# V1.net
KiCad netlist of a schematic drawn in EAGLE
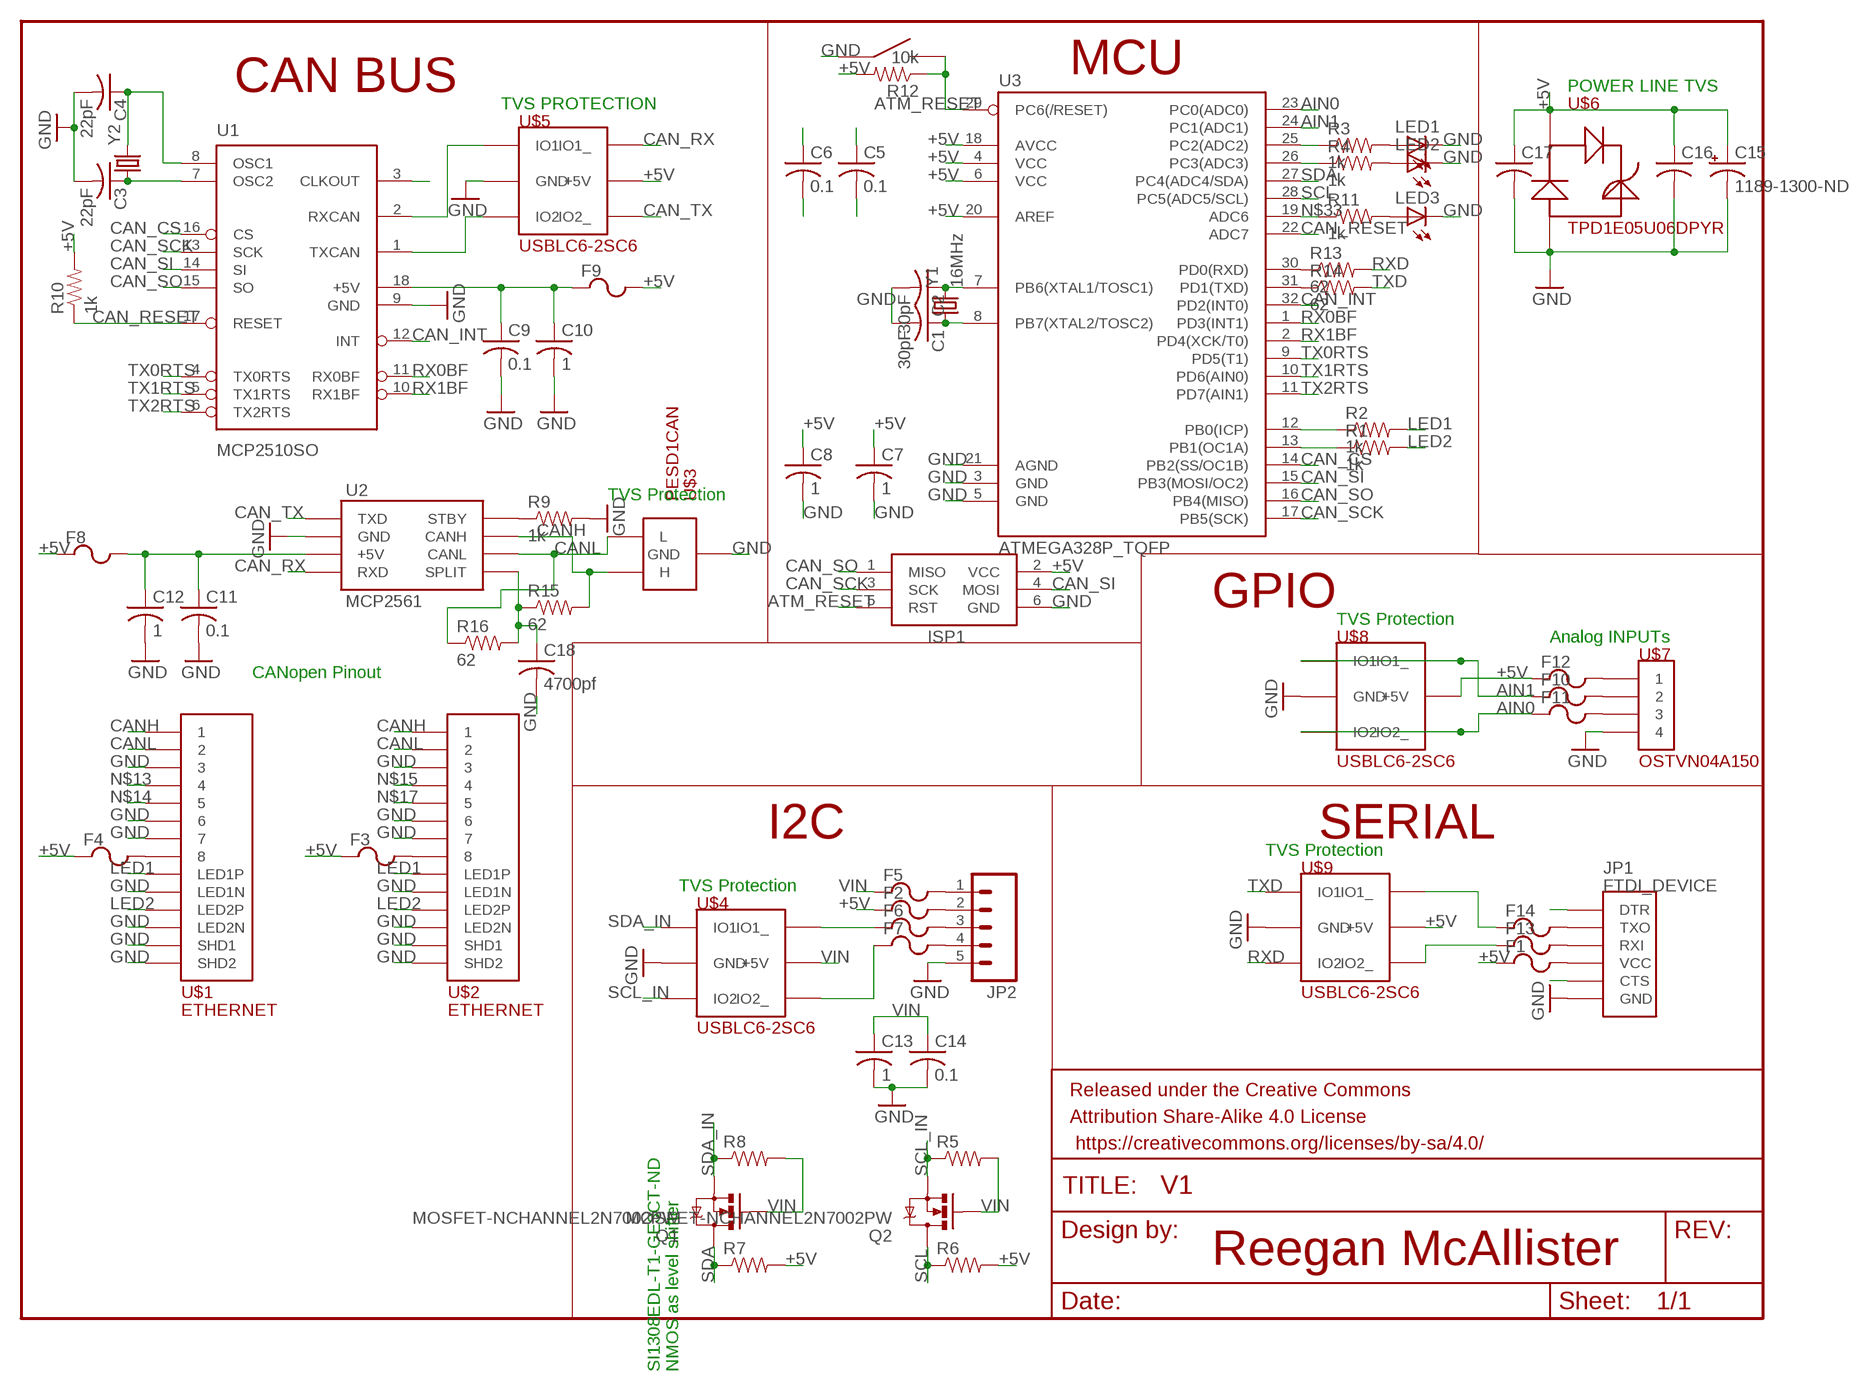
[diagram p0: schematic, sheet 1]

(export (version "E")
  (design (tool "Eeschema 10.0.6"))
  (components
    (comp (ref "C1")
      (value "30pF")
      (footprint "eagle-import:C0603K")
      (libsource (lib "eagle-import") (part "C-USC0603K"))
    )
    (comp (ref "C2")
      (value "30pF")
      (footprint "eagle-import:C0603K")
      (libsource (lib "eagle-import") (part "C-USC0603K"))
    )
    (comp (ref "C3")
      (value "22pF")
      (footprint "eagle-import:C0603K")
      (libsource (lib "eagle-import") (part "C-USC0603K"))
    )
    (comp (ref "C4")
      (value "22pF")
      (footprint "eagle-import:C0603K")
      (libsource (lib "eagle-import") (part "C-USC0603K"))
    )
    (comp (ref "C5")
      (value "0.1")
      (footprint "eagle-import:C0603K")
      (libsource (lib "eagle-import") (part "C-USC0603K"))
    )
    (comp (ref "C6")
      (value "0.1")
      (footprint "eagle-import:C0603K")
      (libsource (lib "eagle-import") (part "C-USC0603K"))
    )
    (comp (ref "C7")
      (value "1")
      (footprint "eagle-import:C0603K")
      (libsource (lib "eagle-import") (part "C-USC0603K"))
    )
    (comp (ref "C8")
      (value "1")
      (footprint "eagle-import:C0603K")
      (libsource (lib "eagle-import") (part "C-USC0603K"))
    )
    (comp (ref "C9")
      (value "0.1")
      (footprint "eagle-import:C0603K")
      (libsource (lib "eagle-import") (part "C-USC0603K"))
    )
    (comp (ref "C10")
      (value "1")
      (footprint "eagle-import:C0603K")
      (libsource (lib "eagle-import") (part "C-USC0603K"))
    )
    (comp (ref "C11")
      (value "0.1")
      (footprint "eagle-import:C0603K")
      (libsource (lib "eagle-import") (part "C-USC0603K"))
    )
    (comp (ref "C12")
      (value "1")
      (footprint "eagle-import:C0603K")
      (libsource (lib "eagle-import") (part "C-USC0603K"))
    )
    (comp (ref "C13")
      (value "1")
      (footprint "eagle-import:C0603K")
      (libsource (lib "eagle-import") (part "C-USC0603K"))
    )
    (comp (ref "C14")
      (value "0.1")
      (footprint "eagle-import:C0603K")
      (libsource (lib "eagle-import") (part "C-USC0603K"))
    )
    (comp (ref "C15")
      (value "1189-1300-ND")
      (footprint "eagle-import:1189-1300-ND")
      (libsource (lib "eagle-import") (part "1189-1300-ND"))
    )
    (comp (ref "C16")
      (value "C-USC0603K")
      (footprint "eagle-import:C0603K")
      (libsource (lib "eagle-import") (part "C-USC0603K"))
    )
    (comp (ref "C17")
      (value "C-USC0603K")
      (footprint "eagle-import:C0603K")
      (libsource (lib "eagle-import") (part "C-USC0603K"))
    )
    (comp (ref "C18")
      (value "4700pf")
      (footprint "eagle-import:C0603K")
      (libsource (lib "eagle-import") (part "C-USC0603K"))
    )
    (comp (ref "F1")
      (value "POLYFUSE")
      (footprint "eagle-import:1206")
      (libsource (lib "eagle-import") (part "POLYFUSE"))
    )
    (comp (ref "F2")
      (value "POLYFUSE")
      (footprint "eagle-import:1206")
      (libsource (lib "eagle-import") (part "POLYFUSE"))
    )
    (comp (ref "F3")
      (value "POLYFUSE")
      (footprint "eagle-import:1206")
      (libsource (lib "eagle-import") (part "POLYFUSE"))
    )
    (comp (ref "F4")
      (value "POLYFUSE")
      (footprint "eagle-import:1206")
      (libsource (lib "eagle-import") (part "POLYFUSE"))
    )
    (comp (ref "F5")
      (value "POLYFUSE")
      (footprint "eagle-import:1206")
      (libsource (lib "eagle-import") (part "POLYFUSE"))
    )
    (comp (ref "F6")
      (value "POLYFUSE")
      (footprint "eagle-import:1206")
      (libsource (lib "eagle-import") (part "POLYFUSE"))
    )
    (comp (ref "F7")
      (value "POLYFUSE")
      (footprint "eagle-import:1206")
      (libsource (lib "eagle-import") (part "POLYFUSE"))
    )
    (comp (ref "F8")
      (value "POLYFUSE")
      (footprint "eagle-import:1206")
      (libsource (lib "eagle-import") (part "POLYFUSE"))
    )
    (comp (ref "F9")
      (value "POLYFUSE")
      (footprint "eagle-import:1206")
      (libsource (lib "eagle-import") (part "POLYFUSE"))
    )
    (comp (ref "F10")
      (value "POLYFUSE")
      (footprint "eagle-import:1206")
      (libsource (lib "eagle-import") (part "POLYFUSE"))
    )
    (comp (ref "F11")
      (value "POLYFUSE")
      (footprint "eagle-import:1206")
      (libsource (lib "eagle-import") (part "POLYFUSE"))
    )
    (comp (ref "F12")
      (value "POLYFUSE")
      (footprint "eagle-import:1206")
      (libsource (lib "eagle-import") (part "POLYFUSE"))
    )
    (comp (ref "F13")
      (value "POLYFUSE")
      (footprint "eagle-import:1206")
      (libsource (lib "eagle-import") (part "POLYFUSE"))
    )
    (comp (ref "F14")
      (value "POLYFUSE")
      (footprint "eagle-import:1206")
      (libsource (lib "eagle-import") (part "POLYFUSE"))
    )
    (comp (ref "FRAME1")
      (value "FRAME-LETTERNO_PACKAGE")
      (footprint "eagle-import:DUMMY")
      (fields (field (name "DESIGNER") "Nobody"))
      (libsource (lib "eagle-import") (part "FRAME-LETTERNO_PACKAGE"))
    )
    (comp (ref "ISP1")
      (value "AVRISP-BOX")
      (footprint "eagle-import:AVRISP-BOX")
      (libsource (lib "eagle-import") (part "AVRISP-BOX"))
    )
    (comp (ref "JP1")
      (value "FTDI_DEVICE")
      (footprint "eagle-import:FTDI_DEVICE_SIDE")
      (libsource (lib "eagle-import") (part "FTDI_DEVICE"))
    )
    (comp (ref "JP2")
      (value "M05NO_SILK")
      (footprint "eagle-import:1X05_NO_SILK")
      (libsource (lib "eagle-import") (part "M05NO_SILK"))
    )
    (comp (ref "LED1")
      (value "LEDCHIPLED_0805")
      (footprint "eagle-import:CHIPLED_0805")
      (libsource (lib "eagle-import") (part "LEDCHIPLED_0805"))
    )
    (comp (ref "LED2")
      (value "LEDCHIPLED_0805")
      (footprint "eagle-import:CHIPLED_0805")
      (libsource (lib "eagle-import") (part "LEDCHIPLED_0805"))
    )
    (comp (ref "LED3")
      (value "LEDCHIPLED_0805")
      (footprint "eagle-import:CHIPLED_0805")
      (libsource (lib "eagle-import") (part "LEDCHIPLED_0805"))
    )
    (comp (ref "Q1")
      (value "MOSFET-NCHANNEL2N7002PW")
      (footprint "eagle-import:SOT323")
      (libsource (lib "eagle-import") (part "MOSFET-NCHANNEL2N7002PW"))
    )
    (comp (ref "Q2")
      (value "MOSFET-NCHANNEL2N7002PW")
      (footprint "eagle-import:SOT323")
      (libsource (lib "eagle-import") (part "MOSFET-NCHANNEL2N7002PW"))
    )
    (comp (ref "R1")
      (value "1k")
      (footprint "eagle-import:0603-RES")
      (libsource (lib "eagle-import") (part "RESISTOR0603-RES"))
    )
    (comp (ref "R2")
      (value "1k")
      (footprint "eagle-import:0603-RES")
      (libsource (lib "eagle-import") (part "RESISTOR0603-RES"))
    )
    (comp (ref "R3")
      (value "1k")
      (footprint "eagle-import:0603-RES")
      (libsource (lib "eagle-import") (part "RESISTOR0603-RES"))
    )
    (comp (ref "R4")
      (value "1k")
      (footprint "eagle-import:0603-RES")
      (libsource (lib "eagle-import") (part "RESISTOR0603-RES"))
    )
    (comp (ref "R5")
      (value "RESISTOR0603-RES")
      (footprint "eagle-import:0603-RES")
      (libsource (lib "eagle-import") (part "RESISTOR0603-RES"))
    )
    (comp (ref "R6")
      (value "RESISTOR0603-RES")
      (footprint "eagle-import:0603-RES")
      (libsource (lib "eagle-import") (part "RESISTOR0603-RES"))
    )
    (comp (ref "R7")
      (value "RESISTOR0603-RES")
      (footprint "eagle-import:0603-RES")
      (libsource (lib "eagle-import") (part "RESISTOR0603-RES"))
    )
    (comp (ref "R8")
      (value "RESISTOR0603-RES")
      (footprint "eagle-import:0603-RES")
      (libsource (lib "eagle-import") (part "RESISTOR0603-RES"))
    )
    (comp (ref "R9")
      (value "1k")
      (footprint "eagle-import:0603-RES")
      (libsource (lib "eagle-import") (part "RESISTOR0603-RES"))
    )
    (comp (ref "R10")
      (value "1k")
      (footprint "eagle-import:0603-RES")
      (libsource (lib "eagle-import") (part "RESISTOR0603-RES"))
    )
    (comp (ref "R11")
      (value "1k")
      (footprint "eagle-import:0603-RES")
      (libsource (lib "eagle-import") (part "RESISTOR0603-RES"))
    )
    (comp (ref "R12")
      (value "10k")
      (footprint "eagle-import:0603-RES")
      (libsource (lib "eagle-import") (part "RESISTOR0603-RES"))
    )
    (comp (ref "R13")
      (value "62")
      (footprint "eagle-import:0603-RES")
      (libsource (lib "eagle-import") (part "RESISTOR0603-RES"))
    )
    (comp (ref "R14")
      (value "62")
      (footprint "eagle-import:0603-RES")
      (libsource (lib "eagle-import") (part "RESISTOR0603-RES"))
    )
    (comp (ref "R15")
      (value "62")
      (footprint "eagle-import:0603-RES")
      (libsource (lib "eagle-import") (part "RESISTOR0603-RES"))
    )
    (comp (ref "R16")
      (value "62")
      (footprint "eagle-import:0603-RES")
      (libsource (lib "eagle-import") (part "RESISTOR0603-RES"))
    )
    (comp (ref "U$1")
      (value "ETHERNET")
      (footprint "eagle-import:A122645-ND")
      (libsource (lib "eagle-import") (part "ETHERNET"))
    )
    (comp (ref "U$2")
      (value "ETHERNET")
      (footprint "eagle-import:A122645-ND")
      (libsource (lib "eagle-import") (part "ETHERNET"))
    )
    (comp (ref "U$3")
      (value "PESD1CAN")
      (footprint "eagle-import:PESD1CAN")
      (libsource (lib "eagle-import") (part "PESD1CAN"))
    )
    (comp (ref "U$4")
      (value "USBLC6-2SC6")
      (footprint "eagle-import:USBLC6-2SC6")
      (libsource (lib "eagle-import") (part "USBLC6-2SC6"))
    )
    (comp (ref "U$5")
      (value "USBLC6-2SC6")
      (footprint "eagle-import:USBLC6-2SC6")
      (libsource (lib "eagle-import") (part "USBLC6-2SC6"))
    )
    (comp (ref "U$6")
      (value "TPD1E05U06DPYR")
      (footprint "eagle-import:2-XDFN")
      (libsource (lib "eagle-import") (part "TPD1E05U06DPYR"))
    )
    (comp (ref "U$7")
      (value "OSTVN04A150")
      (footprint "eagle-import:OSTVN04A1450")
      (libsource (lib "eagle-import") (part "OSTVN04A150"))
    )
    (comp (ref "U$8")
      (value "USBLC6-2SC6")
      (footprint "eagle-import:USBLC6-2SC6")
      (libsource (lib "eagle-import") (part "USBLC6-2SC6"))
    )
    (comp (ref "U$9")
      (value "USBLC6-2SC6")
      (footprint "eagle-import:USBLC6-2SC6")
      (libsource (lib "eagle-import") (part "USBLC6-2SC6"))
    )
    (comp (ref "U$10")
      (value "EG4621CT-ND")
      (footprint "eagle-import:EG4621CT-ND")
      (libsource (lib "eagle-import") (part "EG4621CT-ND"))
    )
    (comp (ref "U1")
      (value "MCP2510SO")
      (footprint "eagle-import:SO-18W")
      (libsource (lib "eagle-import") (part "MCP2510SO"))
    )
    (comp (ref "U2")
      (value "MCP2561")
      (footprint "eagle-import:DIP8")
      (libsource (lib "eagle-import") (part "MCP2561"))
    )
    (comp (ref "U3")
      (value "ATMEGA328P_TQFP")
      (footprint "eagle-import:TQFP32-08")
      (libsource (lib "eagle-import") (part "ATMEGA328P_TQFP"))
    )
    (comp (ref "Y1")
      (value "16MHz")
      (footprint "eagle-import:HC49US")
      (libsource (lib "eagle-import") (part "CRYSTALHC49US"))
    )
    (comp (ref "Y2")
      (value "CRYSTALHC49US")
      (footprint "eagle-import:HC49US")
      (libsource (lib "eagle-import") (part "CRYSTALHC49US"))
    )
  )
  (nets
    (net (code "1") (name "/+5V") (class "Default")
      (node (ref "C15") (pin "P$2") (pinfunction "+_P$2") (pintype "passive"))
      (node (ref "C16") (pin "1") (pinfunction "1_1") (pintype "passive"))
      (node (ref "C17") (pin "1") (pinfunction "1_1") (pintype "passive"))
      (node (ref "C5") (pin "1") (pinfunction "1_1") (pintype "passive"))
      (node (ref "C6") (pin "1") (pinfunction "1_1") (pintype "passive"))
      (node (ref "C7") (pin "1") (pinfunction "1_1") (pintype "passive"))
      (node (ref "C8") (pin "1") (pinfunction "1_1") (pintype "passive"))
      (node (ref "F1") (pin "1") (pinfunction "1_1") (pintype "passive"))
      (node (ref "F12") (pin "1") (pinfunction "1_1") (pintype "passive"))
      (node (ref "F2") (pin "1") (pinfunction "1_1") (pintype "passive"))
      (node (ref "F3") (pin "1") (pinfunction "1_1") (pintype "passive"))
      (node (ref "F4") (pin "1") (pinfunction "1_1") (pintype "passive"))
      (node (ref "F8") (pin "1") (pinfunction "1_1") (pintype "passive"))
      (node (ref "F9") (pin "2") (pinfunction "2_2") (pintype "passive"))
      (node (ref "ISP1") (pin "2") (pinfunction "VCC_2") (pintype "power_in"))
      (node (ref "R10") (pin "2") (pinfunction "2_2") (pintype "passive"))
      (node (ref "R12") (pin "2") (pinfunction "2_2") (pintype "passive"))
      (node (ref "R6") (pin "2") (pinfunction "2_2") (pintype "passive"))
      (node (ref "R7") (pin "2") (pinfunction "2_2") (pintype "passive"))
      (node (ref "U$5") (pin "P$5") (pinfunction "+5V_P$5") (pintype "bidirectional"))
      (node (ref "U$6") (pin "P$1") (pinfunction "P$1_P$1") (pintype "bidirectional"))
      (node (ref "U$8") (pin "P$5") (pinfunction "+5V_P$5") (pintype "bidirectional"))
      (node (ref "U$9") (pin "P$5") (pinfunction "+5V_P$5") (pintype "bidirectional"))
      (node (ref "U3") (pin "18") (pinfunction "AVCC_18") (pintype "bidirectional"))
      (node (ref "U3") (pin "20") (pinfunction "AREF_20") (pintype "bidirectional"))
      (node (ref "U3") (pin "4") (pinfunction "VCC_4") (pintype "bidirectional"))
      (node (ref "U3") (pin "6") (pinfunction "VCC_6") (pintype "bidirectional"))
    )
    (net (code "2") (name "/AIN0") (class "Default")
      (node (ref "F11") (pin "1") (pinfunction "1_1") (pintype "passive"))
      (node (ref "U$8") (pin "P$3") (pinfunction "IO2_P$3") (pintype "bidirectional"))
      (node (ref "U$8") (pin "P$4") (pinfunction "IO2__P$4") (pintype "bidirectional"))
      (node (ref "U3") (pin "23") (pinfunction "PC0(ADC0)_23") (pintype "bidirectional"))
    )
    (net (code "3") (name "/AIN1") (class "Default")
      (node (ref "F10") (pin "1") (pinfunction "1_1") (pintype "passive"))
      (node (ref "U$8") (pin "P$1") (pinfunction "IO1_P$1") (pintype "bidirectional"))
      (node (ref "U$8") (pin "P$6") (pinfunction "IO1__P$6") (pintype "bidirectional"))
      (node (ref "U3") (pin "24") (pinfunction "PC1(ADC1)_24") (pintype "bidirectional"))
    )
    (net (code "4") (name "/ATM_RESET") (class "Default")
      (node (ref "ISP1") (pin "5") (pinfunction "RST_5") (pintype "output"))
      (node (ref "R12") (pin "1") (pinfunction "1_1") (pintype "passive"))
      (node (ref "U$10") (pin "P$3") (pinfunction "P$2_P$3") (pintype "bidirectional"))
      (node (ref "U$10") (pin "P$4") (pinfunction "P$2_P$4") (pintype "bidirectional"))
      (node (ref "U3") (pin "29") (pinfunction "PC6(/RESET)_29") (pintype "bidirectional"))
    )
    (net (code "5") (name "/CANH") (class "Default")
      (node (ref "R15") (pin "2") (pinfunction "2_2") (pintype "passive"))
      (node (ref "U$1") (pin "P$1") (pinfunction "1_P$1") (pintype "bidirectional"))
      (node (ref "U$2") (pin "P$1") (pinfunction "1_P$1") (pintype "bidirectional"))
      (node (ref "U$3") (pin "P$1") (pinfunction "H_P$1") (pintype "bidirectional"))
      (node (ref "U2") (pin "P$7") (pinfunction "CANH_P$7") (pintype "bidirectional"))
    )
    (net (code "6") (name "/CANL") (class "Default")
      (node (ref "R16") (pin "1") (pinfunction "1_1") (pintype "passive"))
      (node (ref "U$1") (pin "P$2") (pinfunction "2_P$2") (pintype "bidirectional"))
      (node (ref "U$2") (pin "P$2") (pinfunction "2_P$2") (pintype "bidirectional"))
      (node (ref "U$3") (pin "P$2") (pinfunction "L_P$2") (pintype "bidirectional"))
      (node (ref "U2") (pin "P$6") (pinfunction "CANL_P$6") (pintype "bidirectional"))
    )
    (net (code "7") (name "/CAN_CS") (class "Default")
      (node (ref "U1") (pin "16") (pinfunction "CS_16") (pintype "input"))
      (node (ref "U3") (pin "14") (pinfunction "PB2(SS/OC1B)_14") (pintype "bidirectional"))
    )
    (net (code "8") (name "/CAN_INT") (class "Default")
      (node (ref "U1") (pin "12") (pinfunction "INT_12") (pintype "output"))
      (node (ref "U3") (pin "32") (pinfunction "PD2(INT0)_32") (pintype "bidirectional"))
    )
    (net (code "9") (name "/CAN_RESET") (class "Default")
      (node (ref "R10") (pin "1") (pinfunction "1_1") (pintype "passive"))
      (node (ref "U1") (pin "17") (pinfunction "RESET_17") (pintype "input"))
      (node (ref "U3") (pin "22") (pinfunction "ADC7_22") (pintype "bidirectional"))
    )
    (net (code "10") (name "/CAN_RX") (class "Default")
      (node (ref "U$5") (pin "P$6") (pinfunction "IO1__P$6") (pintype "bidirectional"))
      (node (ref "U2") (pin "P$4") (pinfunction "RXD_P$4") (pintype "bidirectional"))
    )
    (net (code "11") (name "/CAN_SCK") (class "Default")
      (node (ref "ISP1") (pin "3") (pinfunction "SCK_3") (pintype "output"))
      (node (ref "U1") (pin "13") (pinfunction "SCK_13") (pintype "input"))
      (node (ref "U3") (pin "17") (pinfunction "PB5(SCK)_17") (pintype "bidirectional"))
    )
    (net (code "12") (name "/CAN_SI") (class "Default")
      (node (ref "ISP1") (pin "4") (pinfunction "MOSI_4") (pintype "output"))
      (node (ref "U1") (pin "14") (pinfunction "SI_14") (pintype "input"))
      (node (ref "U3") (pin "15") (pinfunction "PB3(MOSI/OC2)_15") (pintype "bidirectional"))
    )
    (net (code "13") (name "/CAN_SO") (class "Default")
      (node (ref "ISP1") (pin "1") (pinfunction "MISO_1") (pintype "input"))
      (node (ref "U1") (pin "15") (pinfunction "SO_15") (pintype "output"))
      (node (ref "U3") (pin "16") (pinfunction "PB4(MISO)_16") (pintype "bidirectional"))
    )
    (net (code "14") (name "/CAN_TX") (class "Default")
      (node (ref "U$5") (pin "P$4") (pinfunction "IO2__P$4") (pintype "bidirectional"))
      (node (ref "U2") (pin "P$1") (pinfunction "TXD_P$1") (pintype "bidirectional"))
    )
    (net (code "15") (name "/LED1") (class "Default")
      (node (ref "R2") (pin "2") (pinfunction "2_2") (pintype "passive"))
      (node (ref "U$1") (pin "P$10") (pinfunction "LED1P_P$10") (pintype "bidirectional"))
      (node (ref "U$2") (pin "P$10") (pinfunction "LED1P_P$10") (pintype "bidirectional"))
    )
    (net (code "16") (name "/LED2") (class "Default")
      (node (ref "R1") (pin "2") (pinfunction "2_2") (pintype "passive"))
      (node (ref "U$1") (pin "P$12") (pinfunction "LED2P_P$12") (pintype "bidirectional"))
      (node (ref "U$2") (pin "P$12") (pinfunction "LED2P_P$12") (pintype "bidirectional"))
    )
    (net (code "17") (name "/N$13") (class "Default")
      (node (ref "U$1") (pin "P$4") (pinfunction "4_P$4") (pintype "bidirectional"))
    )
    (net (code "18") (name "/N$14") (class "Default")
      (node (ref "U$1") (pin "P$5") (pinfunction "5_P$5") (pintype "bidirectional"))
    )
    (net (code "19") (name "/N$15") (class "Default")
      (node (ref "U$2") (pin "P$4") (pinfunction "4_P$4") (pintype "bidirectional"))
    )
    (net (code "20") (name "/N$17") (class "Default")
      (node (ref "U$2") (pin "P$5") (pinfunction "5_P$5") (pintype "bidirectional"))
    )
    (net (code "21") (name "/N$33") (class "Default")
      (node (ref "R11") (pin "1") (pinfunction "1_1") (pintype "passive"))
      (node (ref "U3") (pin "19") (pinfunction "ADC6_19") (pintype "bidirectional"))
    )
    (net (code "22") (name "/RX0BF") (class "Default")
      (node (ref "U1") (pin "11") (pinfunction "RX0BF_11") (pintype "output"))
      (node (ref "U3") (pin "1") (pinfunction "PD3(INT1)_1") (pintype "bidirectional"))
    )
    (net (code "23") (name "/RX1BF") (class "Default")
      (node (ref "U1") (pin "10") (pinfunction "RX1BF_10") (pintype "output"))
      (node (ref "U3") (pin "2") (pinfunction "PD4(XCK/T0)_2") (pintype "bidirectional"))
    )
    (net (code "24") (name "/RXD") (class "Default")
      (node (ref "R13") (pin "2") (pinfunction "2_2") (pintype "passive"))
      (node (ref "U$9") (pin "P$3") (pinfunction "IO2_P$3") (pintype "bidirectional"))
    )
    (net (code "25") (name "/SCL") (class "Default")
      (node (ref "Q2") (pin "3") (pinfunction "D_3") (pintype "passive"))
      (node (ref "R6") (pin "1") (pinfunction "1_1") (pintype "passive"))
      (node (ref "U3") (pin "28") (pinfunction "PC5(ADC5/SCL)_28") (pintype "bidirectional"))
    )
    (net (code "26") (name "/SCL_IN") (class "Default")
      (node (ref "Q2") (pin "2") (pinfunction "S_2") (pintype "passive"))
      (node (ref "R5") (pin "1") (pinfunction "1_1") (pintype "passive"))
      (node (ref "U$4") (pin "P$3") (pinfunction "IO2_P$3") (pintype "bidirectional"))
    )
    (net (code "27") (name "/SDA") (class "Default")
      (node (ref "Q1") (pin "3") (pinfunction "D_3") (pintype "passive"))
      (node (ref "R7") (pin "1") (pinfunction "1_1") (pintype "passive"))
      (node (ref "U3") (pin "27") (pinfunction "PC4(ADC4/SDA)_27") (pintype "bidirectional"))
    )
    (net (code "28") (name "/SDA_IN") (class "Default")
      (node (ref "Q1") (pin "2") (pinfunction "S_2") (pintype "passive"))
      (node (ref "R8") (pin "1") (pinfunction "1_1") (pintype "passive"))
      (node (ref "U$4") (pin "P$1") (pinfunction "IO1_P$1") (pintype "bidirectional"))
    )
    (net (code "29") (name "/TX0RTS") (class "Default")
      (node (ref "U1") (pin "4") (pinfunction "TX0RTS_4") (pintype "input"))
      (node (ref "U3") (pin "9") (pinfunction "PD5(T1)_9") (pintype "bidirectional"))
    )
    (net (code "30") (name "/TX1RTS") (class "Default")
      (node (ref "U1") (pin "5") (pinfunction "TX1RTS_5") (pintype "input"))
      (node (ref "U3") (pin "10") (pinfunction "PD6(AIN0)_10") (pintype "bidirectional"))
    )
    (net (code "31") (name "/TX2RTS") (class "Default")
      (node (ref "U1") (pin "6") (pinfunction "TX2RTS_6") (pintype "input"))
      (node (ref "U3") (pin "11") (pinfunction "PD7(AIN1)_11") (pintype "bidirectional"))
    )
    (net (code "32") (name "/TXD") (class "Default")
      (node (ref "R14") (pin "2") (pinfunction "2_2") (pintype "passive"))
      (node (ref "U$9") (pin "P$1") (pinfunction "IO1_P$1") (pintype "bidirectional"))
    )
    (net (code "33") (name "/VIN") (class "Default")
      (node (ref "C13") (pin "1") (pinfunction "1_1") (pintype "passive"))
      (node (ref "C14") (pin "1") (pinfunction "1_1") (pintype "passive"))
      (node (ref "F5") (pin "1") (pinfunction "1_1") (pintype "passive"))
      (node (ref "Q1") (pin "1") (pinfunction "G_1") (pintype "passive"))
      (node (ref "Q2") (pin "1") (pinfunction "G_1") (pintype "passive"))
      (node (ref "R5") (pin "2") (pinfunction "2_2") (pintype "passive"))
      (node (ref "R8") (pin "2") (pinfunction "2_2") (pintype "passive"))
      (node (ref "U$4") (pin "P$5") (pinfunction "+5V_P$5") (pintype "bidirectional"))
    )
    (net (code "34") (name "GND") (class "Default")
      (node (ref "C1") (pin "2") (pinfunction "2_2") (pintype "passive"))
      (node (ref "C10") (pin "2") (pinfunction "2_2") (pintype "passive"))
      (node (ref "C11") (pin "2") (pinfunction "2_2") (pintype "passive"))
      (node (ref "C12") (pin "2") (pinfunction "2_2") (pintype "passive"))
      (node (ref "C13") (pin "2") (pinfunction "2_2") (pintype "passive"))
      (node (ref "C14") (pin "2") (pinfunction "2_2") (pintype "passive"))
      (node (ref "C15") (pin "P$1") (pinfunction "-_P$1") (pintype "passive"))
      (node (ref "C16") (pin "2") (pinfunction "2_2") (pintype "passive"))
      (node (ref "C17") (pin "2") (pinfunction "2_2") (pintype "passive"))
      (node (ref "C18") (pin "2") (pinfunction "2_2") (pintype "passive"))
      (node (ref "C2") (pin "2") (pinfunction "2_2") (pintype "passive"))
      (node (ref "C3") (pin "2") (pinfunction "2_2") (pintype "passive"))
      (node (ref "C4") (pin "2") (pinfunction "2_2") (pintype "passive"))
      (node (ref "C5") (pin "2") (pinfunction "2_2") (pintype "passive"))
      (node (ref "C6") (pin "2") (pinfunction "2_2") (pintype "passive"))
      (node (ref "C7") (pin "2") (pinfunction "2_2") (pintype "passive"))
      (node (ref "C8") (pin "2") (pinfunction "2_2") (pintype "passive"))
      (node (ref "C9") (pin "2") (pinfunction "2_2") (pintype "passive"))
      (node (ref "ISP1") (pin "6") (pinfunction "GND_6") (pintype "power_in"))
      (node (ref "JP1") (pin "P$6") (pinfunction "GND_P$6") (pintype "bidirectional"))
      (node (ref "JP2") (pin "5") (pinfunction "5_5") (pintype "passive"))
      (node (ref "LED1") (pin "C") (pinfunction "C_C") (pintype "passive"))
      (node (ref "LED2") (pin "C") (pinfunction "C_C") (pintype "passive"))
      (node (ref "LED3") (pin "C") (pinfunction "C_C") (pintype "passive"))
      (node (ref "R9") (pin "2") (pinfunction "2_2") (pintype "passive"))
      (node (ref "U$1") (pin "P$11") (pinfunction "LED2N_P$11") (pintype "bidirectional"))
      (node (ref "U$1") (pin "P$13") (pinfunction "SHD1_P$13") (pintype "bidirectional"))
      (node (ref "U$1") (pin "P$14") (pinfunction "SHD2_P$14") (pintype "bidirectional"))
      (node (ref "U$1") (pin "P$3") (pinfunction "3_P$3") (pintype "bidirectional"))
      (node (ref "U$1") (pin "P$6") (pinfunction "6_P$6") (pintype "bidirectional"))
      (node (ref "U$1") (pin "P$7") (pinfunction "7_P$7") (pintype "bidirectional"))
      (node (ref "U$1") (pin "P$9") (pinfunction "LED1N_P$9") (pintype "bidirectional"))
      (node (ref "U$10") (pin "P$1") (pinfunction "P$1_P$1") (pintype "bidirectional"))
      (node (ref "U$10") (pin "P$2") (pinfunction "P$1_P$2") (pintype "bidirectional"))
      (node (ref "U$2") (pin "P$11") (pinfunction "LED2N_P$11") (pintype "bidirectional"))
      (node (ref "U$2") (pin "P$13") (pinfunction "SHD1_P$13") (pintype "bidirectional"))
      (node (ref "U$2") (pin "P$14") (pinfunction "SHD2_P$14") (pintype "bidirectional"))
      (node (ref "U$2") (pin "P$3") (pinfunction "3_P$3") (pintype "bidirectional"))
      (node (ref "U$2") (pin "P$6") (pinfunction "6_P$6") (pintype "bidirectional"))
      (node (ref "U$2") (pin "P$7") (pinfunction "7_P$7") (pintype "bidirectional"))
      (node (ref "U$2") (pin "P$9") (pinfunction "LED1N_P$9") (pintype "bidirectional"))
      (node (ref "U$3") (pin "P$3") (pinfunction "GND_P$3") (pintype "bidirectional"))
      (node (ref "U$4") (pin "P$2") (pinfunction "GND_P$2") (pintype "bidirectional"))
      (node (ref "U$5") (pin "P$2") (pinfunction "GND_P$2") (pintype "bidirectional"))
      (node (ref "U$6") (pin "P$2") (pinfunction "P$2_P$2") (pintype "bidirectional"))
      (node (ref "U$7") (pin "P$4") (pinfunction "4_P$4") (pintype "bidirectional"))
      (node (ref "U$8") (pin "P$2") (pinfunction "GND_P$2") (pintype "bidirectional"))
      (node (ref "U$9") (pin "P$2") (pinfunction "GND_P$2") (pintype "bidirectional"))
      (node (ref "U1") (pin "9") (pinfunction "GND_9") (pintype "bidirectional"))
      (node (ref "U2") (pin "P$2") (pinfunction "GND_P$2") (pintype "bidirectional"))
      (node (ref "U3") (pin "21") (pinfunction "AGND_21") (pintype "bidirectional"))
      (node (ref "U3") (pin "3") (pinfunction "GND_3") (pintype "bidirectional"))
      (node (ref "U3") (pin "5") (pinfunction "GND_5") (pintype "bidirectional"))
    )
    (net (code "35") (name "Net-(F2-Pad2)") (class "Default")
      (node (ref "F2") (pin "2") (pinfunction "2_2") (pintype "passive"))
      (node (ref "JP2") (pin "2") (pinfunction "2_2") (pintype "passive"))
    )
    (net (code "36") (name "Net-(F5-Pad2)") (class "Default")
      (node (ref "F5") (pin "2") (pinfunction "2_2") (pintype "passive"))
      (node (ref "JP2") (pin "1") (pinfunction "1_1") (pintype "passive"))
    )
    (net (code "37") (name "Net-(F6-Pad2)") (class "Default")
      (node (ref "F6") (pin "2") (pinfunction "2_2") (pintype "passive"))
      (node (ref "JP2") (pin "3") (pinfunction "3_3") (pintype "passive"))
    )
    (net (code "38") (name "Net-(F7-Pad2)") (class "Default")
      (node (ref "F7") (pin "2") (pinfunction "2_2") (pintype "passive"))
      (node (ref "JP2") (pin "4") (pinfunction "4_4") (pintype "passive"))
    )
    (net (code "39") (name "Net-(JP1-RXI)") (class "Default")
      (node (ref "F13") (pin "2") (pinfunction "2_2") (pintype "passive"))
      (node (ref "JP1") (pin "P$3") (pinfunction "RXI_P$3") (pintype "bidirectional"))
    )
    (net (code "40") (name "Net-(JP1-TXO)") (class "Default")
      (node (ref "F14") (pin "2") (pinfunction "2_2") (pintype "passive"))
      (node (ref "JP1") (pin "P$2") (pinfunction "TXO_P$2") (pintype "bidirectional"))
    )
    (net (code "41") (name "Net-(JP1-VCC)") (class "Default")
      (node (ref "F1") (pin "2") (pinfunction "2_2") (pintype "passive"))
      (node (ref "JP1") (pin "P$4") (pinfunction "VCC_P$4") (pintype "bidirectional"))
    )
    (net (code "42") (name "Net-(LED1-PadA)") (class "Default")
      (node (ref "LED1") (pin "A") (pinfunction "A_A") (pintype "passive"))
      (node (ref "R3") (pin "2") (pinfunction "2_2") (pintype "passive"))
    )
    (net (code "43") (name "Net-(LED2-PadA)") (class "Default")
      (node (ref "LED2") (pin "A") (pinfunction "A_A") (pintype "passive"))
      (node (ref "R4") (pin "2") (pinfunction "2_2") (pintype "passive"))
    )
    (net (code "44") (name "Net-(LED3-PadA)") (class "Default")
      (node (ref "LED3") (pin "A") (pinfunction "A_A") (pintype "passive"))
      (node (ref "R11") (pin "2") (pinfunction "2_2") (pintype "passive"))
    )
    (net (code "45") (name "Net-(U$1-8)") (class "Default")
      (node (ref "F4") (pin "2") (pinfunction "2_2") (pintype "passive"))
      (node (ref "U$1") (pin "P$8") (pinfunction "8_P$8") (pintype "bidirectional"))
    )
    (net (code "46") (name "Net-(U$2-8)") (class "Default")
      (node (ref "F3") (pin "2") (pinfunction "2_2") (pintype "passive"))
      (node (ref "U$2") (pin "P$8") (pinfunction "8_P$8") (pintype "bidirectional"))
    )
    (net (code "47") (name "Net-(U$4-IO1_)") (class "Default")
      (node (ref "F6") (pin "1") (pinfunction "1_1") (pintype "passive"))
      (node (ref "U$4") (pin "P$6") (pinfunction "IO1__P$6") (pintype "bidirectional"))
    )
    (net (code "48") (name "Net-(U$4-IO2_)") (class "Default")
      (node (ref "F7") (pin "1") (pinfunction "1_1") (pintype "passive"))
      (node (ref "U$4") (pin "P$4") (pinfunction "IO2__P$4") (pintype "bidirectional"))
    )
    (net (code "49") (name "Net-(U$5-IO1)") (class "Default")
      (node (ref "U$5") (pin "P$1") (pinfunction "IO1_P$1") (pintype "bidirectional"))
      (node (ref "U1") (pin "2") (pinfunction "RXCAN_2") (pintype "input"))
    )
    (net (code "50") (name "Net-(U$5-IO2)") (class "Default")
      (node (ref "U$5") (pin "P$3") (pinfunction "IO2_P$3") (pintype "bidirectional"))
      (node (ref "U1") (pin "1") (pinfunction "TXCAN_1") (pintype "output"))
    )
    (net (code "51") (name "Net-(U$7-1)") (class "Default")
      (node (ref "F12") (pin "2") (pinfunction "2_2") (pintype "passive"))
      (node (ref "U$7") (pin "P$1") (pinfunction "1_P$1") (pintype "bidirectional"))
    )
    (net (code "52") (name "Net-(U$7-2)") (class "Default")
      (node (ref "F10") (pin "2") (pinfunction "2_2") (pintype "passive"))
      (node (ref "U$7") (pin "P$2") (pinfunction "2_P$2") (pintype "bidirectional"))
    )
    (net (code "53") (name "Net-(U$7-3)") (class "Default")
      (node (ref "F11") (pin "2") (pinfunction "2_2") (pintype "passive"))
      (node (ref "U$7") (pin "P$3") (pinfunction "3_P$3") (pintype "bidirectional"))
    )
    (net (code "54") (name "Net-(U$9-IO1_)") (class "Default")
      (node (ref "F14") (pin "1") (pinfunction "1_1") (pintype "passive"))
      (node (ref "U$9") (pin "P$6") (pinfunction "IO1__P$6") (pintype "bidirectional"))
    )
    (net (code "55") (name "Net-(U$9-IO2_)") (class "Default")
      (node (ref "F13") (pin "1") (pinfunction "1_1") (pintype "passive"))
      (node (ref "U$9") (pin "P$4") (pinfunction "IO2__P$4") (pintype "bidirectional"))
    )
    (net (code "56") (name "Net-(U1-+5V)") (class "Default")
      (node (ref "C10") (pin "1") (pinfunction "1_1") (pintype "passive"))
      (node (ref "C9") (pin "1") (pinfunction "1_1") (pintype "passive"))
      (node (ref "F9") (pin "1") (pinfunction "1_1") (pintype "passive"))
      (node (ref "U1") (pin "18") (pinfunction "+5V_18") (pintype "bidirectional"))
    )
    (net (code "57") (name "Net-(U1-OSC1)") (class "Default")
      (node (ref "C4") (pin "1") (pinfunction "1_1") (pintype "passive"))
      (node (ref "U1") (pin "8") (pinfunction "OSC1_8") (pintype "input"))
      (node (ref "Y2") (pin "2") (pinfunction "2_2") (pintype "passive"))
    )
    (net (code "58") (name "Net-(U1-OSC2)") (class "Default")
      (node (ref "C3") (pin "1") (pinfunction "1_1") (pintype "passive"))
      (node (ref "U1") (pin "7") (pinfunction "OSC2_7") (pintype "output"))
      (node (ref "Y2") (pin "1") (pinfunction "1_1") (pintype "passive"))
    )
    (net (code "59") (name "Net-(U2-+5V)") (class "Default")
      (node (ref "C11") (pin "1") (pinfunction "1_1") (pintype "passive"))
      (node (ref "C12") (pin "1") (pinfunction "1_1") (pintype "passive"))
      (node (ref "F8") (pin "2") (pinfunction "2_2") (pintype "passive"))
      (node (ref "U2") (pin "P$3") (pinfunction "+5V_P$3") (pintype "bidirectional"))
    )
    (net (code "60") (name "Net-(U2-SPLIT)") (class "Default")
      (node (ref "C18") (pin "1") (pinfunction "1_1") (pintype "passive"))
      (node (ref "R15") (pin "1") (pinfunction "1_1") (pintype "passive"))
      (node (ref "R16") (pin "2") (pinfunction "2_2") (pintype "passive"))
      (node (ref "U2") (pin "P$5") (pinfunction "SPLIT_P$5") (pintype "bidirectional"))
    )
    (net (code "61") (name "Net-(U2-STBY)") (class "Default")
      (node (ref "R9") (pin "1") (pinfunction "1_1") (pintype "passive"))
      (node (ref "U2") (pin "P$8") (pinfunction "STBY_P$8") (pintype "bidirectional"))
    )
    (net (code "62") (name "Net-(U3-PB0(ICP))") (class "Default")
      (node (ref "R2") (pin "1") (pinfunction "1_1") (pintype "passive"))
      (node (ref "U3") (pin "12") (pinfunction "PB0(ICP)_12") (pintype "bidirectional"))
    )
    (net (code "63") (name "Net-(U3-PB1(OC1A))") (class "Default")
      (node (ref "R1") (pin "1") (pinfunction "1_1") (pintype "passive"))
      (node (ref "U3") (pin "13") (pinfunction "PB1(OC1A)_13") (pintype "bidirectional"))
    )
    (net (code "64") (name "Net-(U3-PB6(XTAL1{slash}TOSC1))") (class "Default")
      (node (ref "C2") (pin "1") (pinfunction "1_1") (pintype "passive"))
      (node (ref "U3") (pin "7") (pinfunction "PB6(XTAL1/TOSC1)_7") (pintype "bidirectional"))
      (node (ref "Y1") (pin "2") (pinfunction "2_2") (pintype "passive"))
    )
    (net (code "65") (name "Net-(U3-PB7(XTAL2{slash}TOSC2))") (class "Default")
      (node (ref "C1") (pin "1") (pinfunction "1_1") (pintype "passive"))
      (node (ref "U3") (pin "8") (pinfunction "PB7(XTAL2/TOSC2)_8") (pintype "bidirectional"))
      (node (ref "Y1") (pin "1") (pinfunction "1_1") (pintype "passive"))
    )
    (net (code "66") (name "Net-(U3-PC2(ADC2))") (class "Default")
      (node (ref "R3") (pin "1") (pinfunction "1_1") (pintype "passive"))
      (node (ref "U3") (pin "25") (pinfunction "PC2(ADC2)_25") (pintype "bidirectional"))
    )
    (net (code "67") (name "Net-(U3-PC3(ADC3))") (class "Default")
      (node (ref "R4") (pin "1") (pinfunction "1_1") (pintype "passive"))
      (node (ref "U3") (pin "26") (pinfunction "PC3(ADC3)_26") (pintype "bidirectional"))
    )
    (net (code "68") (name "Net-(U3-PD0(RXD))") (class "Default")
      (node (ref "R13") (pin "1") (pinfunction "1_1") (pintype "passive"))
      (node (ref "U3") (pin "30") (pinfunction "PD0(RXD)_30") (pintype "bidirectional"))
    )
    (net (code "69") (name "Net-(U3-PD1(TXD))") (class "Default")
      (node (ref "R14") (pin "1") (pinfunction "1_1") (pintype "passive"))
      (node (ref "U3") (pin "31") (pinfunction "PD1(TXD)_31") (pintype "bidirectional"))
    )
    (net (code "70") (name "unconnected-(JP1-CTS-PadP$5)") (class "Default")
      (node (ref "JP1") (pin "P$5") (pinfunction "CTS_P$5") (pintype "bidirectional"))
    )
    (net (code "71") (name "unconnected-(JP1-DTR-PadP$1)") (class "Default")
      (node (ref "JP1") (pin "P$1") (pinfunction "DTR_P$1") (pintype "bidirectional"))
    )
    (net (code "72") (name "unconnected-(U1-CLKOUT-Pad3)") (class "Default")
      (node (ref "U1") (pin "3") (pinfunction "CLKOUT_3") (pintype "output"))
    )
  )
)
